# 06-CM4_USB_HDMI_SDCard.net
KiCad netlist of a schematic drawn in Altium Designer
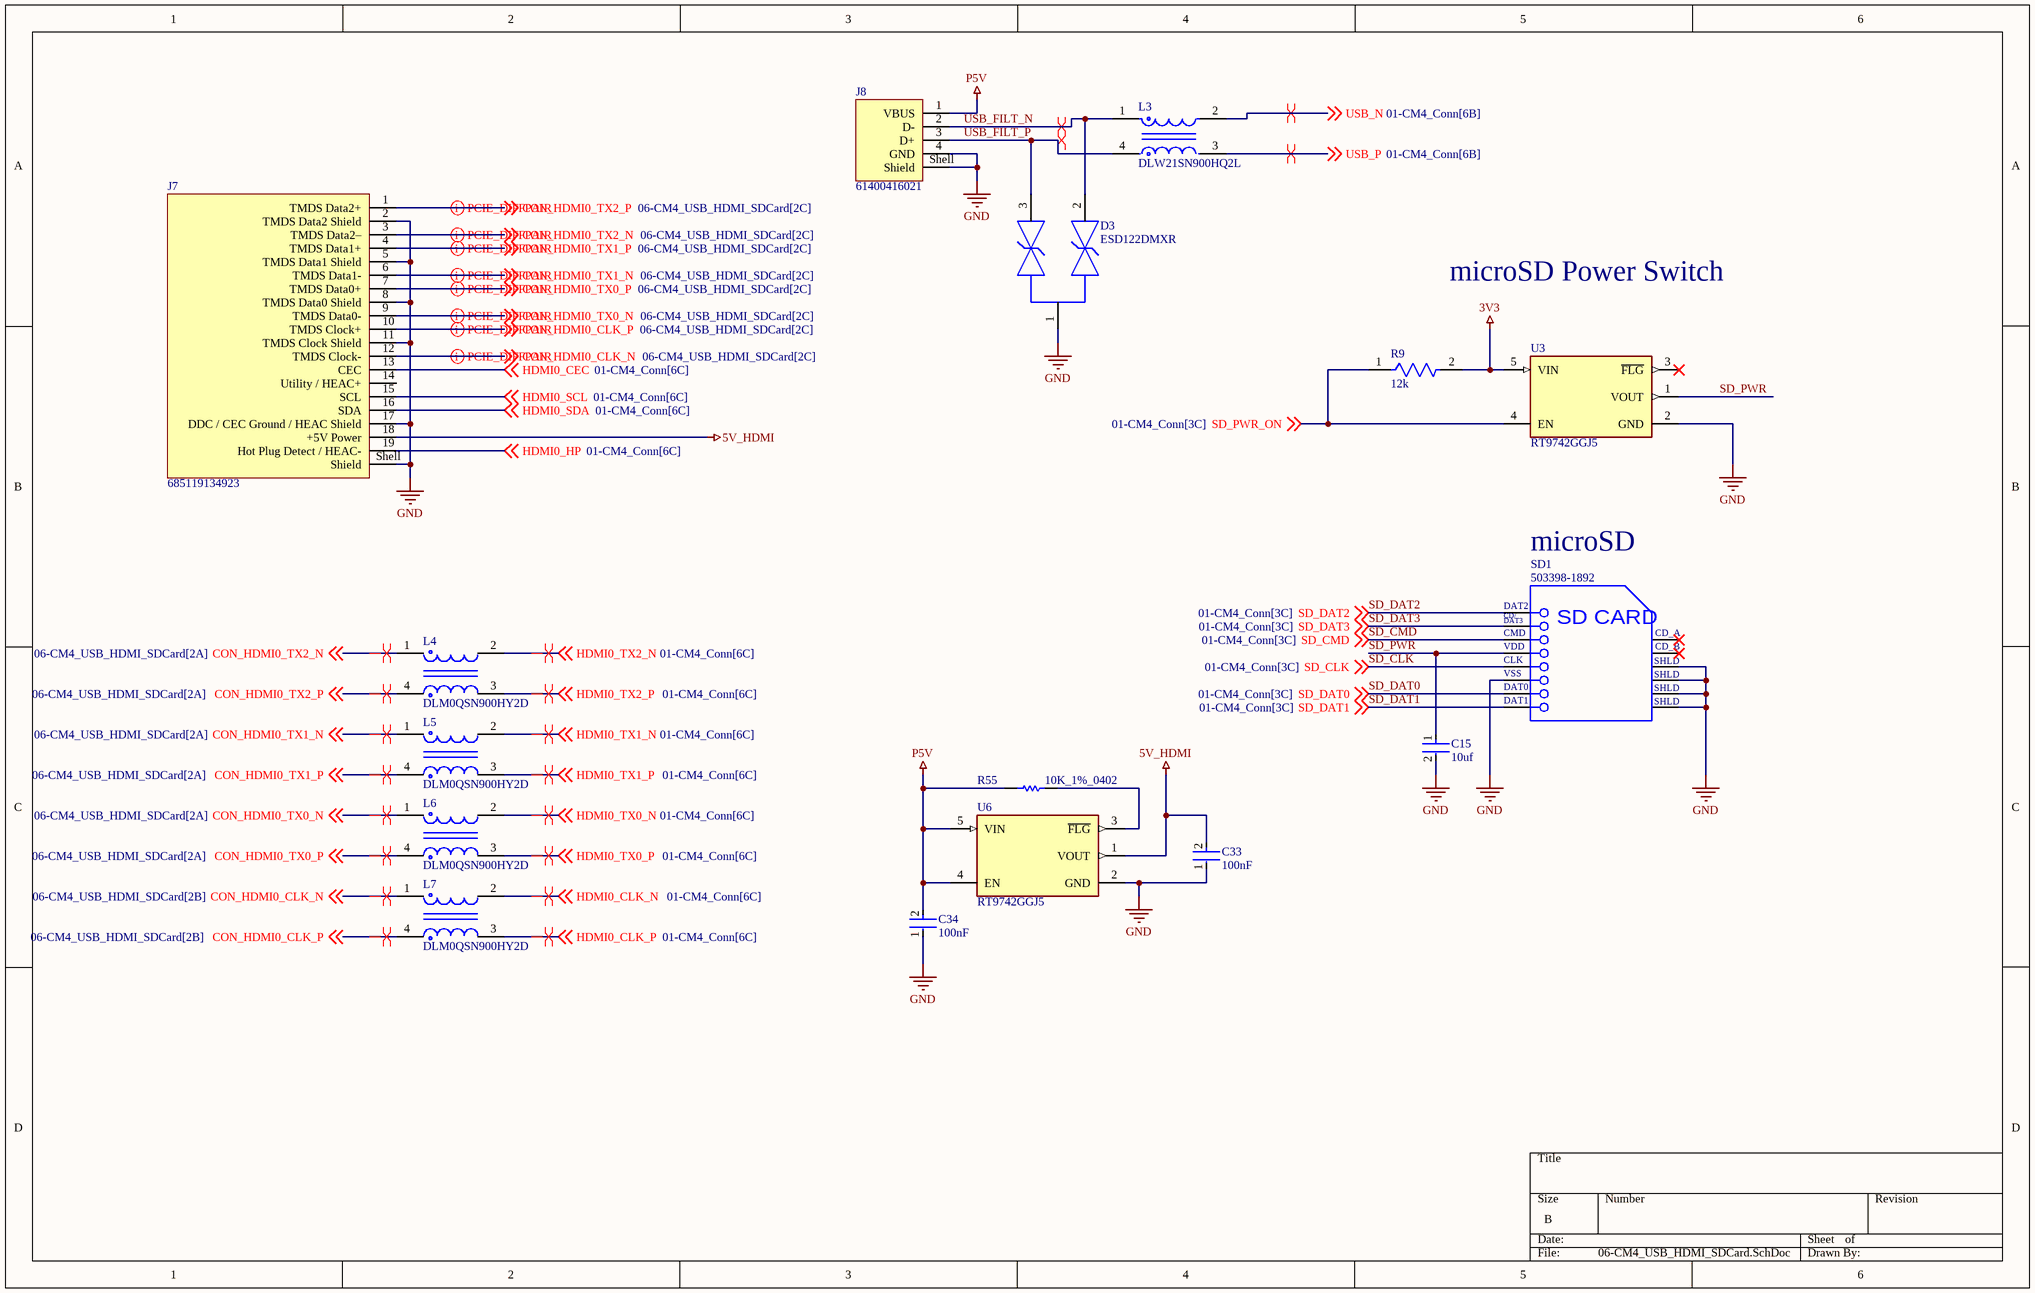
[diagram p0: 06-CM4_USB_HDMI_SDCard.SchDoc]

(export (version "E")
  (design (tool "Eeschema 10.0.6"))
  (components
    (comp (ref "C15")
      (value "10uf")
      (footprint "FP-GRM188-0_2-IPC_C")
      (description "Chip Multilayer Ceramic Capacitors for General Purpose, 0603, 10uF, X5R, 15%, 20%, 35V")
      (fields (field (name "TOLERANCE") "20%"))
      (libsource (lib "Altium Content Vault") (part "11868f565c42a9108669ba33697ecf6"))
    )
    (comp (ref "C33")
      (value "100nF")
      (footprint "FP-GRM15-MFG")
      (description "CAP CER 0.1UF 16V X7R 0402")
      (fields (field (name "MANUFACTURER PART NUMBER") "GRM155R71C104KA88D") (field (name "TOLERANCE") "10%"))
      (libsource (lib "Altium Content Vault") (part "236180d848d6139a670b325ea6854c9"))
    )
    (comp (ref "C34")
      (value "100nF")
      (footprint "FP-GRM15-MFG")
      (description "CAP CER 0.1UF 16V X7R 0402")
      (fields (field (name "MANUFACTURER PART NUMBER") "GRM155R71C104KA88D") (field (name "TOLERANCE") "10%"))
      (libsource (lib "Altium Content Vault") (part "236180d848d6139a670b325ea6854c9"))
    )
    (comp (ref "D3")
      (value "ESD122DMXR")
      (footprint "FP-DMX0003A-MFG")
      (description "TVS DIODE 3.6V 8.4V 3X2SON")
      (libsource (lib "Altium Content Vault") (part "7ac44b7b55cb7aaaff233ca2b760964"))
    )
    (comp (ref "J7")
      (value "685119134923")
      (footprint "685119134923")
      (libsource (lib "Altium Content Vault") (part "HDMI_Type A"))
    )
    (comp (ref "J8")
      (value "61400416021")
      (footprint "61400416021")
      (libsource (lib "Altium Content Vault") (part "USB 2.0_Type A_Receptacle_1 Port"))
    )
    (comp (ref "L3")
      (value "DLW21SN900HQ2L")
      (footprint "FP-DLW21S-MFG")
      (description "Common Mode Choke, 0805, 90Ω @ 100MHz, 0.41Ω, 25%, 280mA")
      (fields (field (name "TOLERANCE") "25%"))
      (libsource (lib "Altium Content Vault") (part "4bfa77fc51c2d0064063899a2a33d23"))
    )
    (comp (ref "L4")
      (value "DLM0QSN900HY2D")
      (footprint "FP-DLM0Q-MFG")
      (description "Chip Common Mode Choke Coil Monolithic 025020 50mA 90Ohm @ 100MHz")
      (libsource (lib "Altium Content Vault") (part "ceb18a25f7f751334f014c631ae0852"))
    )
    (comp (ref "L5")
      (value "DLM0QSN900HY2D")
      (footprint "FP-DLM0Q-MFG")
      (description "Chip Common Mode Choke Coil Monolithic 025020 50mA 90Ohm @ 100MHz")
      (libsource (lib "Altium Content Vault") (part "ceb18a25f7f751334f014c631ae0852"))
    )
    (comp (ref "L6")
      (value "DLM0QSN900HY2D")
      (footprint "FP-DLM0Q-MFG")
      (description "Chip Common Mode Choke Coil Monolithic 025020 50mA 90Ohm @ 100MHz")
      (libsource (lib "Altium Content Vault") (part "ceb18a25f7f751334f014c631ae0852"))
    )
    (comp (ref "L7")
      (value "DLM0QSN900HY2D")
      (footprint "FP-DLM0Q-MFG")
      (description "Chip Common Mode Choke Coil Monolithic 025020 50mA 90Ohm @ 100MHz")
      (libsource (lib "Altium Content Vault") (part "ceb18a25f7f751334f014c631ae0852"))
    )
    (comp (ref "R9")
      (value "12k")
      (footprint "FP-RC0402-0_4-IPC_C")
      (description "RES SMD 12K OHM 1% 1/16W 0402")
      (fields (field (name "TOLERANCE") "1%"))
      (libsource (lib "Altium Content Vault") (part "1029c3af85768c4190bb7ad29bc67b5"))
    )
    (comp (ref "R55")
      (value "10K_1%_0402")
      (footprint "RESC1005X40X25NL10T10")
      (fields (field (name "MANUFACTURER") "Bourns") (field (name "PART NUMBER") "CR0402-FX-1002GLF"))
      (libsource (lib "Altium Content Vault") (part "RES"))
    )
    (comp (ref "SD1")
      (value "503398-1892")
      (footprint "MOLX-503398-1892_V")
      (description "Micro SD Connector, Pitch 1.1 mm, 8 Position, Height 1.4 mm, -25 to 85 degC, RoHS, Tape and Reel")
      (fields (field (name "MANUFACTURER") "Molex"))
      (libsource (lib "Altium Content Vault") (part "CN-SD-8-2SW-4S"))
    )
    (comp (ref "U3")
      (value "RT9742GGJ5")
      (footprint "FP-RT9742GGJ5-IPC_C")
      (description "IC PWR SWTCH N-CHAN 1:1 TSOT23-5")
      (libsource (lib "Altium Content Vault") (part "6b3db7b45087fee8fb60b49bef92a32"))
    )
    (comp (ref "U6")
      (value "RT9742GGJ5")
      (footprint "FP-RT9742GGJ5-IPC_C")
      (description "IC PWR SWTCH N-CHAN 1:1 TSOT23-5")
      (libsource (lib "Altium Content Vault") (part "6b3db7b45087fee8fb60b49bef92a32"))
    )
  )
  (nets
    (net (code "1") (name "/SD_PWR") (class "Default")
      (node (ref "C15") (pin "1") (pinfunction "1_1") (pintype "passive"))
      (node (ref "SD1") (pin "4") (pinfunction "VDD_4") (pintype "passive"))
      (node (ref "U3") (pin "1") (pinfunction "VOUT_1") (pintype "output"))
    )
    (net (code "2") (name "/USB_FILT_N") (class "Default")
      (node (ref "D3") (pin "2") (pinfunction "IO1_2") (pintype "passive"))
      (node (ref "J8") (pin "2") (pinfunction "D-_2") (pintype "passive"))
      (node (ref "L3") (pin "1") (pinfunction "1_1") (pintype "passive"))
    )
    (net (code "3") (name "/USB_FILT_P") (class "Default")
      (node (ref "D3") (pin "3") (pinfunction "IO2_3") (pintype "passive"))
      (node (ref "J8") (pin "3") (pinfunction "D+_3") (pintype "passive"))
      (node (ref "L3") (pin "4") (pinfunction "4_4") (pintype "passive"))
    )
    (net (code "4") (name "3V3") (class "Default")
      (node (ref "R9") (pin "2") (pinfunction "2_2") (pintype "passive"))
      (node (ref "U3") (pin "5") (pinfunction "VIN_5") (pintype "input"))
    )
    (net (code "5") (name "5V_HDMI") (class "Default")
      (node (ref "C33") (pin "2") (pinfunction "2_2") (pintype "passive"))
      (node (ref "J7") (pin "18") (pinfunction "+5V_Power_18") (pintype "passive"))
      (node (ref "U6") (pin "1") (pinfunction "VOUT_1") (pintype "output"))
    )
    (net (code "6") (name "CON_HDMI0_CLK_N") (class "Default")
      (node (ref "J7") (pin "12") (pinfunction "TMDS_Clock-_12") (pintype "passive"))
      (node (ref "L7") (pin "1") (pinfunction "1_1") (pintype "passive"))
    )
    (net (code "7") (name "CON_HDMI0_CLK_P") (class "Default")
      (node (ref "J7") (pin "10") (pinfunction "TMDS_Clock+_10") (pintype "passive"))
      (node (ref "L7") (pin "4") (pinfunction "4_4") (pintype "passive"))
    )
    (net (code "8") (name "CON_HDMI0_TX0_N") (class "Default")
      (node (ref "J7") (pin "9") (pinfunction "TMDS_Data0-_9") (pintype "passive"))
      (node (ref "L6") (pin "1") (pinfunction "1_1") (pintype "passive"))
    )
    (net (code "9") (name "CON_HDMI0_TX0_P") (class "Default")
      (node (ref "J7") (pin "7") (pinfunction "TMDS_Data0+_7") (pintype "passive"))
      (node (ref "L6") (pin "4") (pinfunction "4_4") (pintype "passive"))
    )
    (net (code "10") (name "CON_HDMI0_TX1_N") (class "Default")
      (node (ref "J7") (pin "6") (pinfunction "TMDS_Data1-_6") (pintype "passive"))
      (node (ref "L5") (pin "1") (pinfunction "1_1") (pintype "passive"))
    )
    (net (code "11") (name "CON_HDMI0_TX1_P") (class "Default")
      (node (ref "J7") (pin "4") (pinfunction "TMDS_Data1+_4") (pintype "passive"))
      (node (ref "L5") (pin "4") (pinfunction "4_4") (pintype "passive"))
    )
    (net (code "12") (name "CON_HDMI0_TX2_N") (class "Default")
      (node (ref "J7") (pin "3") (pinfunction "TMDS_Data2–_3") (pintype "passive"))
      (node (ref "L4") (pin "1") (pinfunction "1_1") (pintype "passive"))
    )
    (net (code "13") (name "CON_HDMI0_TX2_P") (class "Default")
      (node (ref "J7") (pin "1") (pinfunction "TMDS_Data2+_1") (pintype "passive"))
      (node (ref "L4") (pin "4") (pinfunction "4_4") (pintype "passive"))
    )
    (net (code "14") (name "GND") (class "Default")
      (node (ref "C15") (pin "2") (pinfunction "2_2") (pintype "passive"))
      (node (ref "C33") (pin "1") (pinfunction "1_1") (pintype "passive"))
      (node (ref "C34") (pin "1") (pinfunction "1_1") (pintype "passive"))
      (node (ref "D3") (pin "1") (pinfunction "GND_1") (pintype "power_in"))
      (node (ref "J7") (pin "11") (pinfunction "TMDS_Clock_Shield_11") (pintype "passive"))
      (node (ref "J7") (pin "17") (pinfunction "DDC_/_CEC_Ground_/_HEAC_Shield_17") (pintype "passive"))
      (node (ref "J7") (pin "2") (pinfunction "TMDS_Data2_Shield_2") (pintype "passive"))
      (node (ref "J7") (pin "5") (pinfunction "TMDS_Data1_Shield_5") (pintype "passive"))
      (node (ref "J7") (pin "8") (pinfunction "TMDS_Data0_Shield_8") (pintype "passive"))
      (node (ref "J7") (pin "Shell") (pinfunction "Shield_Shell") (pintype "passive"))
      (node (ref "J8") (pin "4") (pinfunction "GND_4") (pintype "passive"))
      (node (ref "J8") (pin "Shell") (pinfunction "Shield_Shell") (pintype "passive"))
      (node (ref "SD1") (pin "11") (pinfunction "SHLD_11") (pintype "passive"))
      (node (ref "SD1") (pin "12") (pinfunction "SHLD_12") (pintype "passive"))
      (node (ref "SD1") (pin "13") (pinfunction "SHLD_13") (pintype "passive"))
      (node (ref "SD1") (pin "14") (pinfunction "SHLD_14") (pintype "passive"))
      (node (ref "SD1") (pin "6") (pinfunction "VSS_6") (pintype "passive"))
      (node (ref "U3") (pin "2") (pinfunction "GND_2") (pintype "power_in"))
      (node (ref "U6") (pin "2") (pinfunction "GND_2") (pintype "power_in"))
    )
    (net (code "15") (name "HDMI0_CEC") (class "Default")
      (node (ref "J7") (pin "13") (pinfunction "CEC_13") (pintype "passive"))
    )
    (net (code "16") (name "HDMI0_CLK_N") (class "Default")
      (node (ref "L7") (pin "2") (pinfunction "2_2") (pintype "passive"))
    )
    (net (code "17") (name "HDMI0_CLK_P") (class "Default")
      (node (ref "L7") (pin "3") (pinfunction "3_3") (pintype "passive"))
    )
    (net (code "18") (name "HDMI0_HP") (class "Default")
      (node (ref "J7") (pin "19") (pinfunction "Hot_Plug_Detect_/_HEAC-_19") (pintype "passive"))
    )
    (net (code "19") (name "HDMI0_SCL") (class "Default")
      (node (ref "J7") (pin "15") (pinfunction "SCL_15") (pintype "passive"))
    )
    (net (code "20") (name "HDMI0_SDA") (class "Default")
      (node (ref "J7") (pin "16") (pinfunction "SDA_16") (pintype "passive"))
    )
    (net (code "21") (name "HDMI0_TX0_N") (class "Default")
      (node (ref "L6") (pin "2") (pinfunction "2_2") (pintype "passive"))
    )
    (net (code "22") (name "HDMI0_TX0_P") (class "Default")
      (node (ref "L6") (pin "3") (pinfunction "3_3") (pintype "passive"))
    )
    (net (code "23") (name "HDMI0_TX1_N") (class "Default")
      (node (ref "L5") (pin "2") (pinfunction "2_2") (pintype "passive"))
    )
    (net (code "24") (name "HDMI0_TX1_P") (class "Default")
      (node (ref "L5") (pin "3") (pinfunction "3_3") (pintype "passive"))
    )
    (net (code "25") (name "HDMI0_TX2_N") (class "Default")
      (node (ref "L4") (pin "2") (pinfunction "2_2") (pintype "passive"))
    )
    (net (code "26") (name "HDMI0_TX2_P") (class "Default")
      (node (ref "L4") (pin "3") (pinfunction "3_3") (pintype "passive"))
    )
    (net (code "27") (name "Net-(U6-~{FLG})") (class "Default")
      (node (ref "R55") (pin "2") (pinfunction "2_2") (pintype "passive"))
      (node (ref "U6") (pin "3") (pinfunction "~{FLG}_3") (pintype "output"))
    )
    (net (code "28") (name "P5V") (class "Default")
      (node (ref "C34") (pin "2") (pinfunction "2_2") (pintype "passive"))
      (node (ref "J8") (pin "1") (pinfunction "VBUS_1") (pintype "passive"))
      (node (ref "R55") (pin "1") (pinfunction "1_1") (pintype "passive"))
      (node (ref "U6") (pin "4") (pinfunction "EN_4") (pintype "passive"))
      (node (ref "U6") (pin "5") (pinfunction "VIN_5") (pintype "input"))
    )
    (net (code "29") (name "SD_CLK") (class "Default")
      (node (ref "SD1") (pin "5") (pinfunction "CLK_5") (pintype "passive"))
    )
    (net (code "30") (name "SD_CMD") (class "Default")
      (node (ref "SD1") (pin "3") (pinfunction "CMD_3") (pintype "passive"))
    )
    (net (code "31") (name "SD_DAT0") (class "Default")
      (node (ref "SD1") (pin "7") (pinfunction "DAT0_7") (pintype "passive"))
    )
    (net (code "32") (name "SD_DAT1") (class "Default")
      (node (ref "SD1") (pin "8") (pinfunction "DAT1_8") (pintype "passive"))
    )
    (net (code "33") (name "SD_DAT2") (class "Default")
      (node (ref "SD1") (pin "1") (pinfunction "DAT2_1") (pintype "passive"))
    )
    (net (code "34") (name "SD_DAT3") (class "Default")
      (node (ref "SD1") (pin "2") (pinfunction "CD/DAT3_2") (pintype "passive"))
    )
    (net (code "35") (name "SD_PWR_ON") (class "Default")
      (node (ref "R9") (pin "1") (pinfunction "1_1") (pintype "passive"))
      (node (ref "U3") (pin "4") (pinfunction "EN_4") (pintype "passive"))
    )
    (net (code "36") (name "USB_N") (class "Default")
      (node (ref "L3") (pin "2") (pinfunction "2_2") (pintype "passive"))
    )
    (net (code "37") (name "USB_P") (class "Default")
      (node (ref "L3") (pin "3") (pinfunction "3_3") (pintype "passive"))
    )
    (net (code "38") (name "unconnected-(J7-Utility_{slash}_HEAC+-Pad14)") (class "Default")
      (node (ref "J7") (pin "14") (pinfunction "Utility_/_HEAC+_14") (pintype "passive"))
    )
    (net (code "39") (name "unconnected-(SD1-CD_A-Pad9)") (class "Default")
      (node (ref "SD1") (pin "9") (pinfunction "CD_A_9") (pintype "passive+no_connect"))
    )
    (net (code "40") (name "unconnected-(SD1-CD_B-Pad10)") (class "Default")
      (node (ref "SD1") (pin "10") (pinfunction "CD_B_10") (pintype "passive+no_connect"))
    )
    (net (code "41") (name "unconnected-(U3-~{FLG}-Pad3)") (class "Default")
      (node (ref "U3") (pin "3") (pinfunction "~{FLG}_3") (pintype "output+no_connect"))
    )
  )
)
